# 2015-08-14_11-35-571.net
KiCad netlist of a schematic drawn in Altium Designer
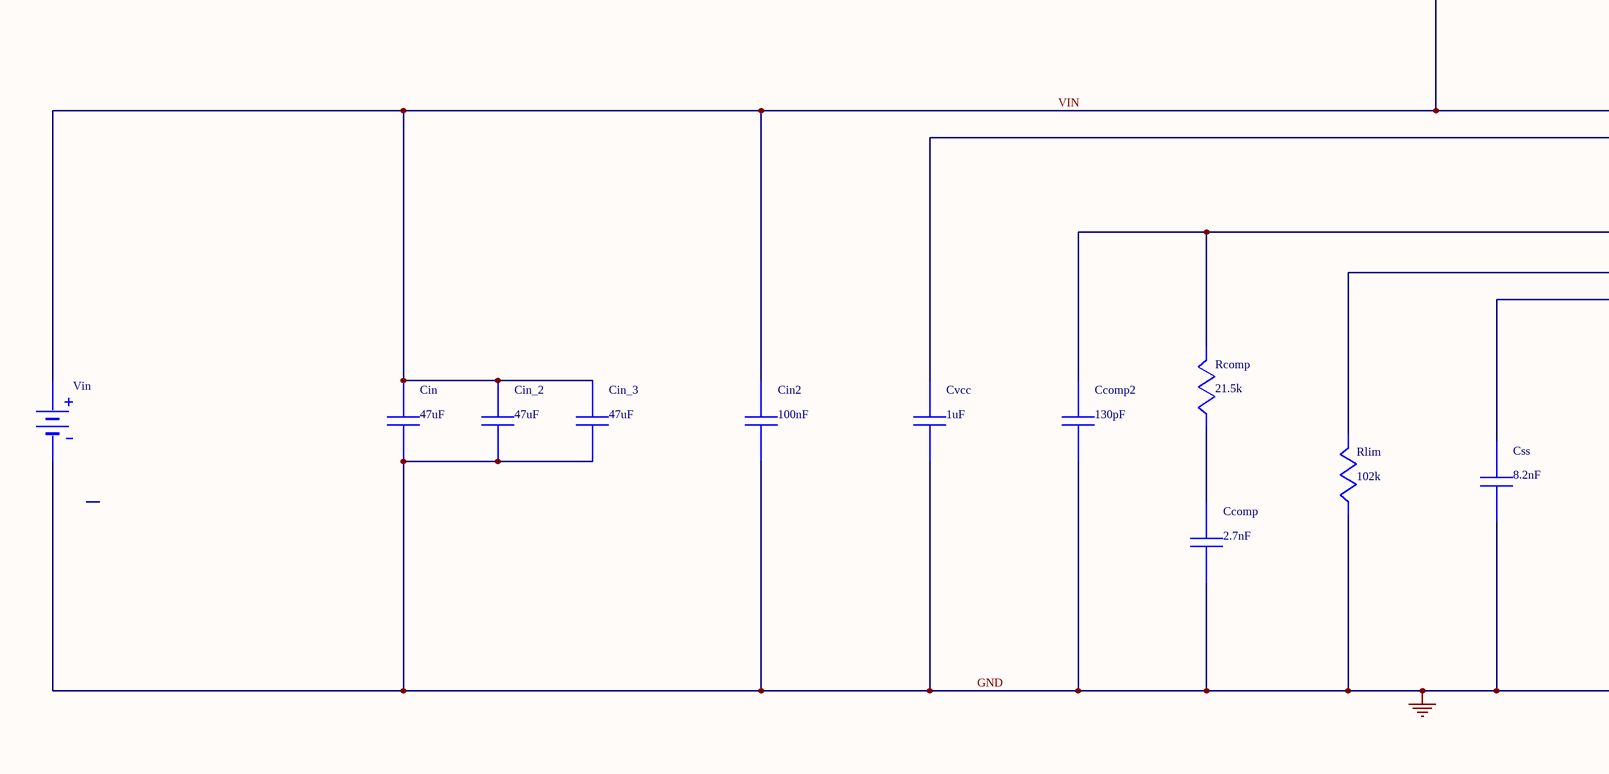
[diagram p0: 2015-08-14_11-35-571.schdoc, left]
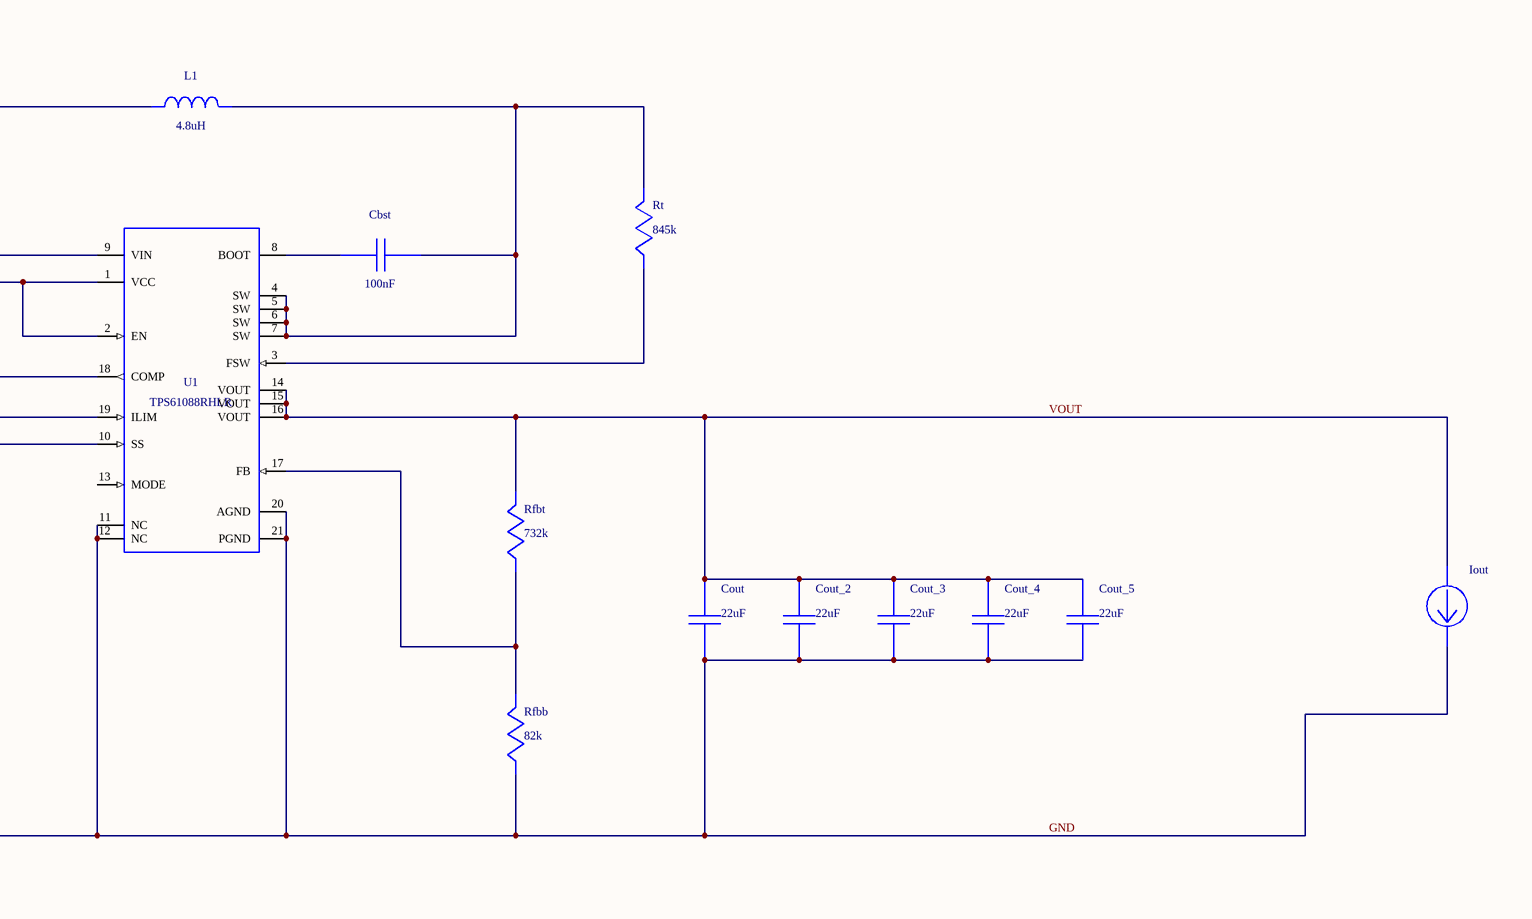
[diagram p1: 2015-08-14_11-35-571.schdoc, right]

(export (version "E")
  (design (tool "Eeschema 10.0.6"))
  (components
    (comp (ref "Cbst")
      (value "100nF")
      (description "08053C104KAT2A")
      (libsource (lib "TI WEBENCH") (part "Cbst"))
    )
    (comp (ref "Ccomp")
      (value "2.7nF")
      (description "CC0805KRX7R9BB27")
      (fields (field (name "MANUFACTURER PART NUMBER") "CC0805KRX7R9BB272"))
      (libsource (lib "TI WEBENCH") (part "Ccomp"))
    )
    (comp (ref "Ccomp2")
      (value "130pF")
      (description "CL21C131JBANNNC")
      (libsource (lib "TI WEBENCH") (part "Ccomp2"))
    )
    (comp (ref "Cin")
      (value "47uF")
      (description "GRM32ER61C476ME1")
      (fields (field (name "MANUFACTURER PART NUMBER") "GRM32ER61C476ME15L"))
      (libsource (lib "TI WEBENCH") (part "Cin"))
    )
    (comp (ref "Cin2")
      (value "100nF")
      (description "GRM155R61C104KA8")
      (fields (field (name "MANUFACTURER PART NUMBER") "GRM155R61C104KA88D"))
      (libsource (lib "TI WEBENCH") (part "Cin2"))
    )
    (comp (ref "Cin_2")
      (value "47uF")
      (description "GRM32ER61C476ME1")
      (fields (field (name "MANUFACTURER PART NUMBER") "GRM32ER61C476ME15L"))
      (libsource (lib "TI WEBENCH") (part "Cin_2"))
    )
    (comp (ref "Cin_3")
      (value "47uF")
      (description "GRM32ER61C476ME1")
      (fields (field (name "MANUFACTURER PART NUMBER") "GRM32ER61C476ME15L"))
      (libsource (lib "TI WEBENCH") (part "Cin_3"))
    )
    (comp (ref "Cout")
      (value "22uF")
      (description "GRM32ER61E226KE1")
      (fields (field (name "MANUFACTURER PART NUMBER") "GRM32ER61E226KE15L"))
      (libsource (lib "TI WEBENCH") (part "Cout"))
    )
    (comp (ref "Cout_2")
      (value "22uF")
      (description "GRM32ER61E226KE1")
      (fields (field (name "MANUFACTURER PART NUMBER") "GRM32ER61E226KE15L"))
      (libsource (lib "TI WEBENCH") (part "Cout_2"))
    )
    (comp (ref "Cout_3")
      (value "22uF")
      (description "GRM32ER61E226KE1")
      (fields (field (name "MANUFACTURER PART NUMBER") "GRM32ER61E226KE15L"))
      (libsource (lib "TI WEBENCH") (part "Cout_3"))
    )
    (comp (ref "Cout_4")
      (value "22uF")
      (description "GRM32ER61E226KE1")
      (fields (field (name "MANUFACTURER PART NUMBER") "GRM32ER61E226KE15L"))
      (libsource (lib "TI WEBENCH") (part "Cout_4"))
    )
    (comp (ref "Cout_5")
      (value "22uF")
      (description "GRM32ER61E226KE1")
      (fields (field (name "MANUFACTURER PART NUMBER") "GRM32ER61E226KE15L"))
      (libsource (lib "TI WEBENCH") (part "Cout_5"))
    )
    (comp (ref "Css")
      (value "8.2nF")
      (description "GRM155R71C822KA0")
      (fields (field (name "MANUFACTURER PART NUMBER") "GRM155R71C822KA01D"))
      (libsource (lib "TI WEBENCH") (part "Css"))
    )
    (comp (ref "Cvcc")
      (value "1uF")
      (description "C1608X5R1A105K")
      (libsource (lib "TI WEBENCH") (part "Cvcc"))
    )
    (comp (ref "Iout") (value "WB_CURRENT_LOAD") (libsource (lib "TI WEBENCH") (part "Iout")))
    (comp (ref "L1") (value "4.8uH") (description "ETQPAF4R8HFA") (libsource (lib "TI WEBENCH") (part "L1")))
    (comp (ref "Rcomp")
      (value "21.5k")
      (description "ERJ-6ENF2152V")
      (libsource (lib "TI WEBENCH") (part "Rcomp"))
    )
    (comp (ref "Rfbb")
      (value "82k")
      (description "RR1220P-823-D")
      (libsource (lib "TI WEBENCH") (part "Rfbb"))
    )
    (comp (ref "Rfbt")
      (value "732k")
      (description "CRCW0402732KFKED")
      (libsource (lib "TI WEBENCH") (part "Rfbt"))
    )
    (comp (ref "Rlim")
      (value "102k")
      (description "ERJ-8ENF1023V")
      (libsource (lib "TI WEBENCH") (part "Rlim"))
    )
    (comp (ref "Rt") (value "845k") (description "ERJ-8ENF8453V") (libsource (lib "TI WEBENCH") (part "Rt")))
    (comp (ref "U1")
      (value "TPS61088RHLR")
      (fields (field (name "PACKAGEREFERENCE") "TPS61088RHLR"))
      (libsource (lib "TI WEBENCH") (part "U1"))
    )
    (comp (ref "Vin") (value "WB_BATTERY") (libsource (lib "TI WEBENCH") (part "Vin")))
  )
  (nets
    (net (code "1") (name "/VIN") (class "Default")
      (node (ref "Cin") (pin "1") (pinfunction "1_1") (pintype "passive"))
      (node (ref "Cin2") (pin "1") (pinfunction "1_1") (pintype "passive"))
      (node (ref "Cin_2") (pin "1") (pinfunction "1_1") (pintype "passive"))
      (node (ref "Cin_3") (pin "1") (pinfunction "1_1") (pintype "passive"))
      (node (ref "L1") (pin "1") (pinfunction "1_1") (pintype "passive"))
      (node (ref "U1") (pin "9") (pinfunction "VIN_9") (pintype "power_in"))
      (node (ref "Vin") (pin "1") (pinfunction "+_1") (pintype "passive"))
    )
    (net (code "2") (name "/VOUT") (class "Default")
      (node (ref "Cout") (pin "1") (pinfunction "1_1") (pintype "passive"))
      (node (ref "Cout_2") (pin "1") (pinfunction "1_1") (pintype "passive"))
      (node (ref "Cout_3") (pin "1") (pinfunction "1_1") (pintype "passive"))
      (node (ref "Cout_4") (pin "1") (pinfunction "1_1") (pintype "passive"))
      (node (ref "Cout_5") (pin "1") (pinfunction "1_1") (pintype "passive"))
      (node (ref "Iout") (pin "1") (pinfunction "+_1") (pintype "passive"))
      (node (ref "Rfbt") (pin "1") (pinfunction "1_1") (pintype "passive"))
      (node (ref "U1") (pin "14") (pinfunction "VOUT_14") (pintype "power_in"))
      (node (ref "U1") (pin "15") (pinfunction "VOUT_15") (pintype "power_in"))
      (node (ref "U1") (pin "16") (pinfunction "VOUT_16") (pintype "power_in"))
    )
    (net (code "3") (name "0") (class "Default")
      (node (ref "Ccomp") (pin "2") (pinfunction "2_2") (pintype "passive"))
      (node (ref "Ccomp2") (pin "2") (pinfunction "2_2") (pintype "passive"))
      (node (ref "Cin") (pin "2") (pinfunction "2_2") (pintype "passive"))
      (node (ref "Cin2") (pin "2") (pinfunction "2_2") (pintype "passive"))
      (node (ref "Cin_2") (pin "2") (pinfunction "2_2") (pintype "passive"))
      (node (ref "Cin_3") (pin "2") (pinfunction "2_2") (pintype "passive"))
      (node (ref "Cout") (pin "2") (pinfunction "2_2") (pintype "passive"))
      (node (ref "Cout_2") (pin "2") (pinfunction "2_2") (pintype "passive"))
      (node (ref "Cout_3") (pin "2") (pinfunction "2_2") (pintype "passive"))
      (node (ref "Cout_4") (pin "2") (pinfunction "2_2") (pintype "passive"))
      (node (ref "Cout_5") (pin "2") (pinfunction "2_2") (pintype "passive"))
      (node (ref "Css") (pin "2") (pinfunction "2_2") (pintype "passive"))
      (node (ref "Cvcc") (pin "2") (pinfunction "2_2") (pintype "passive"))
      (node (ref "Iout") (pin "2") (pinfunction "-_2") (pintype "passive"))
      (node (ref "Rfbb") (pin "2") (pinfunction "2_2") (pintype "passive"))
      (node (ref "Rlim") (pin "2") (pinfunction "2_2") (pintype "passive"))
      (node (ref "U1") (pin "11") (pinfunction "NC_11") (pintype "passive"))
      (node (ref "U1") (pin "12") (pinfunction "NC_12") (pintype "passive"))
      (node (ref "U1") (pin "20") (pinfunction "AGND_20") (pintype "power_in"))
      (node (ref "U1") (pin "21") (pinfunction "PGND_21") (pintype "power_in"))
      (node (ref "Vin") (pin "2") (pinfunction "-_2") (pintype "passive"))
    )
    (net (code "4") (name "Net-(Cbst-Pad2)") (class "Default")
      (node (ref "Cbst") (pin "2") (pinfunction "2_2") (pintype "passive"))
      (node (ref "L1") (pin "2") (pinfunction "2_2") (pintype "passive"))
      (node (ref "Rt") (pin "1") (pinfunction "1_1") (pintype "passive"))
      (node (ref "U1") (pin "4") (pinfunction "SW_4") (pintype "power_in"))
      (node (ref "U1") (pin "5") (pinfunction "SW_5") (pintype "power_in"))
      (node (ref "U1") (pin "6") (pinfunction "SW_6") (pintype "power_in"))
      (node (ref "U1") (pin "7") (pinfunction "SW_7") (pintype "power_in"))
    )
    (net (code "5") (name "Net-(Ccomp-Pad1)") (class "Default")
      (node (ref "Ccomp") (pin "1") (pinfunction "1_1") (pintype "passive"))
      (node (ref "Rcomp") (pin "2") (pinfunction "2_2") (pintype "passive"))
    )
    (net (code "6") (name "Net-(U1-BOOT)") (class "Default")
      (node (ref "Cbst") (pin "1") (pinfunction "1_1") (pintype "passive"))
      (node (ref "U1") (pin "8") (pinfunction "BOOT_8") (pintype "power_in"))
    )
    (net (code "7") (name "Net-(U1-COMP)") (class "Default")
      (node (ref "Ccomp2") (pin "1") (pinfunction "1_1") (pintype "passive"))
      (node (ref "Rcomp") (pin "1") (pinfunction "1_1") (pintype "passive"))
      (node (ref "U1") (pin "18") (pinfunction "COMP_18") (pintype "output"))
    )
    (net (code "8") (name "Net-(U1-EN)") (class "Default")
      (node (ref "Cvcc") (pin "1") (pinfunction "1_1") (pintype "passive"))
      (node (ref "U1") (pin "1") (pinfunction "VCC_1") (pintype "power_in"))
      (node (ref "U1") (pin "2") (pinfunction "EN_2") (pintype "input"))
    )
    (net (code "9") (name "Net-(U1-FB)") (class "Default")
      (node (ref "Rfbb") (pin "1") (pinfunction "1_1") (pintype "passive"))
      (node (ref "Rfbt") (pin "2") (pinfunction "2_2") (pintype "passive"))
      (node (ref "U1") (pin "17") (pinfunction "FB_17") (pintype "input"))
    )
    (net (code "10") (name "Net-(U1-FSW)") (class "Default")
      (node (ref "Rt") (pin "2") (pinfunction "2_2") (pintype "passive"))
      (node (ref "U1") (pin "3") (pinfunction "FSW_3") (pintype "input"))
    )
    (net (code "11") (name "Net-(U1-ILIM)") (class "Default")
      (node (ref "Rlim") (pin "1") (pinfunction "1_1") (pintype "passive"))
      (node (ref "U1") (pin "19") (pinfunction "ILIM_19") (pintype "input"))
    )
    (net (code "12") (name "Net-(U1-SS)") (class "Default")
      (node (ref "Css") (pin "1") (pinfunction "1_1") (pintype "passive"))
      (node (ref "U1") (pin "10") (pinfunction "SS_10") (pintype "input"))
    )
    (net (code "13") (name "unconnected-(U1-MODE-Pad13)") (class "Default")
      (node (ref "U1") (pin "13") (pinfunction "MODE_13") (pintype "input"))
    )
  )
)
